# Driver_using_SON3x3_mosfet.net
KiCad netlist of a schematic drawn in Altium Designer
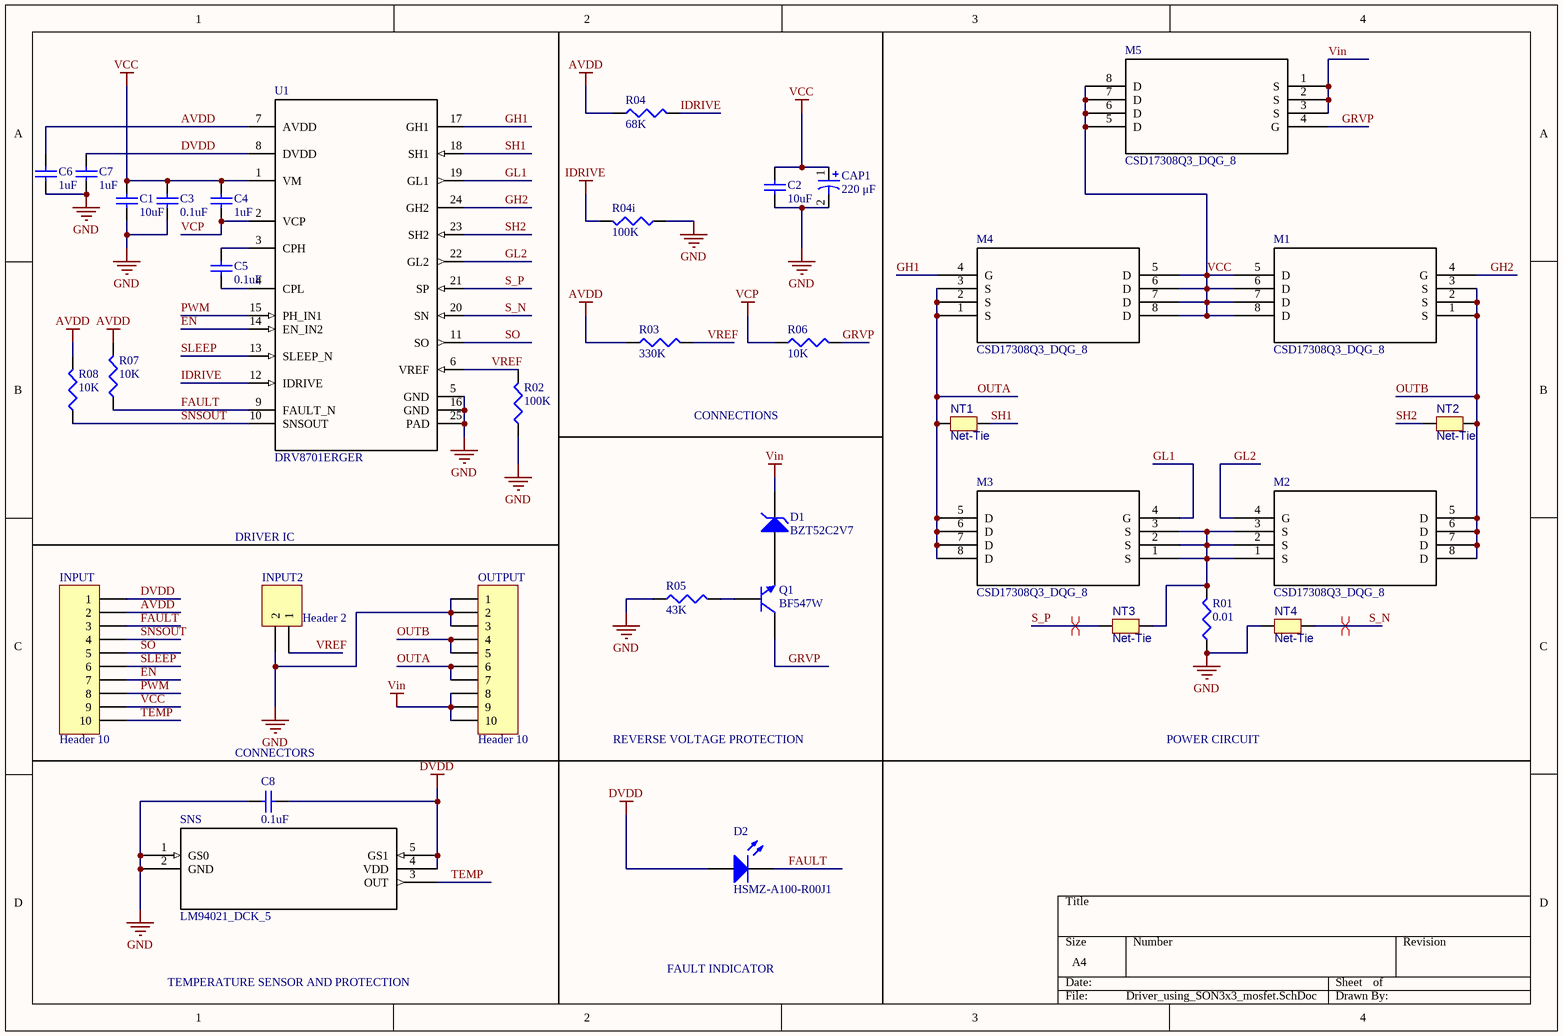
[diagram p0: Driver_using_SON3x3_mosfet.SchDoc]

(export (version "E")
  (design (tool "Eeschema 10.0.6"))
  (components
    (comp (ref "C1")
      (value "10uF")
      (footprint "C1210")
      (description "Capacitor (Semiconductor SIM Model)")
      (fields (field (name "PUBLISHER") "Altium Limited"))
      (libsource (lib "Miscellaneous Devices") (part "Cap Semi"))
    )
    (comp (ref "C2")
      (value "10uF")
      (footprint "C1210")
      (description "Capacitor (Semiconductor SIM Model)")
      (fields (field (name "PUBLISHER") "Altium Limited"))
      (libsource (lib "Miscellaneous Devices") (part "Cap Semi"))
    )
    (comp (ref "C3")
      (value "0.1uF")
      (footprint "1608[0603]")
      (description "Capacitor (Semiconductor SIM Model)")
      (fields (field (name "PUBLISHER") "Altium Limited"))
      (libsource (lib "Miscellaneous Devices") (part "Cap Semi"))
    )
    (comp (ref "C4")
      (value "1uF")
      (footprint "1608[0603]")
      (description "Capacitor (Semiconductor SIM Model)")
      (fields (field (name "PUBLISHER") "Altium Limited"))
      (libsource (lib "Miscellaneous Devices") (part "Cap Semi"))
    )
    (comp (ref "C5")
      (value "0.1uF")
      (footprint "1608[0603]")
      (description "Capacitor (Semiconductor SIM Model)")
      (fields (field (name "PUBLISHER") "Altium Limited"))
      (libsource (lib "Miscellaneous Devices") (part "Cap Semi"))
    )
    (comp (ref "C6")
      (value "1uF")
      (footprint "1608[0603]")
      (description "Capacitor (Semiconductor SIM Model)")
      (fields (field (name "PUBLISHER") "Altium Limited"))
      (libsource (lib "Miscellaneous Devices") (part "Cap Semi"))
    )
    (comp (ref "C7")
      (value "1uF")
      (footprint "1608[0603]")
      (description "Capacitor (Semiconductor SIM Model)")
      (fields (field (name "PUBLISHER") "Altium Limited"))
      (libsource (lib "Miscellaneous Devices") (part "Cap Semi"))
    )
    (comp (ref "C8")
      (value "0.1uF")
      (footprint "1608[0603]")
      (description "Capacitor (Semiconductor SIM Model)")
      (fields (field (name "PUBLISHER") "Altium Limited"))
      (libsource (lib "Miscellaneous Devices") (part "Cap Semi"))
    )
    (comp (ref "CAP1")
      (value "220 μF")
      (footprint "WCAP-ASLL 10x10.5x4.5")
      (description "WCAP-ASLL Aluminum Electrolytic Capacitors , 220 μF; + / - 20%; 35 V , 10 x 10,5")
      (fields
        (field (name "MANUFACTURER") "Wurth Elektronik")
        (field (name "PARTNO") "865060557008")
        (field (name "E-MAIL") "libraries@we-online.com")
        (field (name "CREATED BY") "Karrer Zheng")
      )
      (libsource (lib "WCAP-ASLL_rev15a") (part "WCAP-ASLL 10x10.5x4.5 865060557008"))
    )
    (comp (ref "D1")
      (value "BZT52C2V7")
      (footprint "SOD-123")
      (description "Surface Mount Zener Diode")
      (fields (field (name "PUBLISHER") "Altium Limited"))
      (libsource (lib "Vishay Lite-On Discrete Diode") (part "BZT52C2V7"))
    )
    (comp (ref "D2")
      (value "HSMZ-A100-R00J1")
      (footprint "3.5X2.8X1.9")
      (description "Surface Mount LED Indicator, Red")
      (fields (field (name "PUBLISHER") "Altium Limited"))
      (libsource (lib "Avago Optoelectronic LED") (part "HSMZ-A100-R00J1"))
    )
    (comp (ref "INPUT")
      (value "Header 10")
      (footprint "HDR1X10")
      (description "Header, 10-Pin")
      (fields (field (name "PUBLISHER") "Altium Limited"))
      (libsource (lib "Miscellaneous Connectors") (part "Header 10"))
    )
    (comp (ref "INPUT2")
      (value "Header 2")
      (footprint "HDR1X2")
      (description "Header, 2-Pin")
      (fields (field (name "PUBLISHER") "Altium Limited"))
      (libsource (lib "Miscellaneous Connectors") (part "Header 2"))
    )
    (comp (ref "M1")
      (value "CSD17308Q3_DQG_8")
      (footprint "DQG8")
      (description "Imported")
      (fields
        (field (name "MANUFACTURER") "Texas Instruments")
        (field (name "GENERIC_PART_NUMBER") "CSD17308Q3")
      )
      (libsource (lib "2016-01-31_14-51-58") (part "CSD17308Q3_DQG_8"))
    )
    (comp (ref "M2")
      (value "CSD17308Q3_DQG_8")
      (footprint "DQG8")
      (description "Imported")
      (fields
        (field (name "MANUFACTURER") "Texas Instruments")
        (field (name "GENERIC_PART_NUMBER") "CSD17308Q3")
      )
      (libsource (lib "2016-01-31_14-51-58") (part "CSD17308Q3_DQG_8"))
    )
    (comp (ref "M3")
      (value "CSD17308Q3_DQG_8")
      (footprint "DQG8")
      (description "Imported")
      (fields
        (field (name "MANUFACTURER") "Texas Instruments")
        (field (name "GENERIC_PART_NUMBER") "CSD17308Q3")
      )
      (libsource (lib "2016-01-31_14-51-58") (part "CSD17308Q3_DQG_8"))
    )
    (comp (ref "M4")
      (value "CSD17308Q3_DQG_8")
      (footprint "DQG8")
      (description "Imported")
      (fields
        (field (name "MANUFACTURER") "Texas Instruments")
        (field (name "GENERIC_PART_NUMBER") "CSD17308Q3")
      )
      (libsource (lib "2016-01-31_14-51-58") (part "CSD17308Q3_DQG_8"))
    )
    (comp (ref "M5")
      (value "CSD17308Q3_DQG_8")
      (footprint "DQG8")
      (description "Imported")
      (fields
        (field (name "MANUFACTURER") "Texas Instruments")
        (field (name "GENERIC_PART_NUMBER") "CSD17308Q3")
      )
      (libsource (lib "2016-01-31_14-51-58") (part "CSD17308Q3_DQG_8"))
    )
    (comp (ref "NT1")
      (value "Net-Tie")
      (footprint "NetTieLib:2way_LP")
      (description "Single point connection between nets.")
      (fields (field (name "SYMBOLCREATOR") "codlsc") (field (name "PUBLISHER") "Texas Instruments"))
      (libsource (lib "MiscParts") (part "Net-Tie"))
    )
    (comp (ref "NT2")
      (value "Net-Tie")
      (footprint "2way_LP")
      (description "Single point connection between nets.")
      (fields (field (name "SYMBOLCREATOR") "codlsc") (field (name "PUBLISHER") "Texas Instruments"))
      (libsource (lib "MiscParts") (part "Net-Tie"))
    )
    (comp (ref "NT3")
      (value "Net-Tie")
      (footprint "2way_LP")
      (description "Single point connection between nets.")
      (fields (field (name "SYMBOLCREATOR") "codlsc") (field (name "PUBLISHER") "Texas Instruments"))
      (libsource (lib "MiscParts") (part "Net-Tie"))
    )
    (comp (ref "NT4")
      (value "Net-Tie")
      (footprint "2way_LP")
      (description "Single point connection between nets.")
      (fields (field (name "SYMBOLCREATOR") "codlsc") (field (name "PUBLISHER") "Texas Instruments"))
      (libsource (lib "MiscParts") (part "Net-Tie"))
    )
    (comp (ref "OUTPUT")
      (value "Header 10")
      (footprint "HDR1X10")
      (description "Header, 10-Pin")
      (fields (field (name "PUBLISHER") "Altium Limited"))
      (libsource (lib "") (part "Header 10_1"))
    )
    (comp (ref "Q1")
      (value "BF547W")
      (footprint "SOT323_N")
      (description "NPN 1 GHz Wideband Transistor")
      (fields (field (name "PUBLISHER") "Altium Limited"))
      (libsource (lib "Philips Discrete BJT - RF Transistor") (part "BF547W"))
    )
    (comp (ref "R01")
      (value "0.01")
      (footprint "14-1210")
      (description "Resistor")
      (fields (field (name "PUBLISHER") "Altium Limited"))
      (libsource (lib "Miscellaneous Devices") (part "Res3"))
    )
    (comp (ref "R02")
      (value "100K")
      (footprint "J1-0603")
      (description "Resistor")
      (fields (field (name "PUBLISHER") "Altium Limited"))
      (libsource (lib "Miscellaneous Devices") (part "Res3"))
    )
    (comp (ref "R03")
      (value "330K")
      (footprint "J1-0603")
      (description "Resistor")
      (fields (field (name "PUBLISHER") "Altium Limited"))
      (libsource (lib "Miscellaneous Devices") (part "Res3"))
    )
    (comp (ref "R04")
      (value "68K")
      (footprint "J1-0603")
      (description "Resistor")
      (fields (field (name "PUBLISHER") "Altium Limited"))
      (libsource (lib "Miscellaneous Devices") (part "Res3"))
    )
    (comp (ref "R04i")
      (value "100K")
      (footprint "J1-0603")
      (description "Resistor")
      (fields (field (name "PUBLISHER") "Altium Limited"))
      (libsource (lib "Miscellaneous Devices") (part "Res3"))
    )
    (comp (ref "R05")
      (value "43K")
      (footprint "J1-0603")
      (description "Resistor")
      (fields (field (name "PUBLISHER") "Altium Limited"))
      (libsource (lib "Miscellaneous Devices") (part "Res3"))
    )
    (comp (ref "R06")
      (value "10K")
      (footprint "J1-0603")
      (description "Resistor")
      (fields (field (name "PUBLISHER") "Altium Limited"))
      (libsource (lib "Miscellaneous Devices") (part "Res3"))
    )
    (comp (ref "R07")
      (value "10K")
      (footprint "J1-0603")
      (description "Resistor")
      (fields (field (name "PUBLISHER") "Altium Limited"))
      (libsource (lib "Miscellaneous Devices") (part "Res3"))
    )
    (comp (ref "R08")
      (value "10K")
      (footprint "J1-0603")
      (description "Resistor")
      (fields (field (name "PUBLISHER") "Altium Limited"))
      (libsource (lib "Miscellaneous Devices") (part "Res3"))
    )
    (comp (ref "SNS")
      (value "LM94021_DCK_5")
      (footprint "MAA05A")
      (description "Imported")
      (fields
        (field (name "MANUFACTURER") "Texas Instruments")
        (field (name "MANUFACTURER_PART_NUMBER") "lm94021_dck_5")
      )
      (libsource (lib "2016-02-23_02-52-09") (part "LM94021_DCK_5"))
    )
    (comp (ref "U1")
      (value "DRV8701ERGER")
      (footprint "RGE0024F")
      (description "Imported")
      (fields
        (field (name "ALTERNATE PARTNUMBER") "DRV8701ERGET")
        (field (name "MANUFACTURER") "Texas Instruments")
      )
      (libsource (lib "2016-01-03_22-07-35") (part "DRV8701ERGER"))
    )
  )
  (nets
    (net (code "1") (name "/EN") (class "Default")
      (node (ref "INPUT") (pin "7") (pinfunction "7_7") (pintype "passive"))
      (node (ref "U1") (pin "14") (pinfunction "EN_IN2_14") (pintype "input"))
    )
    (net (code "2") (name "/FAULT") (class "Default")
      (node (ref "D2") (pin "2") (pinfunction "K_2") (pintype "passive"))
      (node (ref "INPUT") (pin "3") (pinfunction "3_3") (pintype "passive"))
      (node (ref "R07") (pin "1") (pinfunction "1_1") (pintype "passive"))
      (node (ref "U1") (pin "9") (pinfunction "FAULT_N_9") (pintype "open_collector"))
    )
    (net (code "3") (name "/GH1") (class "Default")
      (node (ref "M4") (pin "4") (pinfunction "G_4") (pintype "passive"))
      (node (ref "U1") (pin "17") (pinfunction "GH1_17") (pintype "power_in"))
    )
    (net (code "4") (name "/GH2") (class "Default")
      (node (ref "M1") (pin "4") (pinfunction "G_4") (pintype "passive"))
      (node (ref "U1") (pin "24") (pinfunction "GH2_24") (pintype "power_in"))
    )
    (net (code "5") (name "/GL1") (class "Default")
      (node (ref "M3") (pin "4") (pinfunction "G_4") (pintype "passive"))
      (node (ref "U1") (pin "19") (pinfunction "GL1_19") (pintype "output"))
    )
    (net (code "6") (name "/GL2") (class "Default")
      (node (ref "M2") (pin "4") (pinfunction "G_4") (pintype "passive"))
      (node (ref "U1") (pin "22") (pinfunction "GL2_22") (pintype "output"))
    )
    (net (code "7") (name "/GRVP") (class "Default")
      (node (ref "M5") (pin "4") (pinfunction "G_4") (pintype "passive"))
      (node (ref "Q1") (pin "3") (pinfunction "C_3") (pintype "passive"))
      (node (ref "R06") (pin "2") (pinfunction "2_2") (pintype "passive"))
    )
    (net (code "8") (name "/OUTA") (class "Default")
      (node (ref "M3") (pin "5") (pinfunction "D_5") (pintype "passive"))
      (node (ref "M3") (pin "6") (pinfunction "D_6") (pintype "passive"))
      (node (ref "M3") (pin "7") (pinfunction "D_7") (pintype "passive"))
      (node (ref "M3") (pin "8") (pinfunction "D_8") (pintype "passive"))
      (node (ref "M4") (pin "1") (pinfunction "S_1") (pintype "passive"))
      (node (ref "M4") (pin "2") (pinfunction "S_2") (pintype "passive"))
      (node (ref "M4") (pin "3") (pinfunction "S_3") (pintype "passive"))
      (node (ref "NT1") (pin "1") (pinfunction "1_1") (pintype "passive"))
      (node (ref "OUTPUT") (pin "6") (pinfunction "6_6") (pintype "passive"))
      (node (ref "OUTPUT") (pin "7") (pinfunction "7_7") (pintype "passive"))
    )
    (net (code "9") (name "/OUTB") (class "Default")
      (node (ref "M1") (pin "1") (pinfunction "S_1") (pintype "passive"))
      (node (ref "M1") (pin "2") (pinfunction "S_2") (pintype "passive"))
      (node (ref "M1") (pin "3") (pinfunction "S_3") (pintype "passive"))
      (node (ref "M2") (pin "5") (pinfunction "D_5") (pintype "passive"))
      (node (ref "M2") (pin "6") (pinfunction "D_6") (pintype "passive"))
      (node (ref "M2") (pin "7") (pinfunction "D_7") (pintype "passive"))
      (node (ref "M2") (pin "8") (pinfunction "D_8") (pintype "passive"))
      (node (ref "NT2") (pin "2") (pinfunction "2_2") (pintype "passive"))
      (node (ref "OUTPUT") (pin "4") (pinfunction "4_4") (pintype "passive"))
      (node (ref "OUTPUT") (pin "5") (pinfunction "5_5") (pintype "passive"))
    )
    (net (code "10") (name "/PWM") (class "Default")
      (node (ref "INPUT") (pin "8") (pinfunction "8_8") (pintype "passive"))
      (node (ref "U1") (pin "15") (pinfunction "PH_IN1_15") (pintype "input"))
    )
    (net (code "11") (name "/SH1") (class "Default")
      (node (ref "NT1") (pin "2") (pinfunction "2_2") (pintype "passive"))
      (node (ref "U1") (pin "18") (pinfunction "SH1_18") (pintype "input"))
    )
    (net (code "12") (name "/SH2") (class "Default")
      (node (ref "NT2") (pin "1") (pinfunction "1_1") (pintype "passive"))
      (node (ref "U1") (pin "23") (pinfunction "SH2_23") (pintype "input"))
    )
    (net (code "13") (name "/SLEEP") (class "Default")
      (node (ref "INPUT") (pin "6") (pinfunction "6_6") (pintype "passive"))
      (node (ref "U1") (pin "13") (pinfunction "SLEEP_N_13") (pintype "input"))
    )
    (net (code "14") (name "/SNSOUT") (class "Default")
      (node (ref "INPUT") (pin "4") (pinfunction "4_4") (pintype "passive"))
      (node (ref "R08") (pin "1") (pinfunction "1_1") (pintype "passive"))
      (node (ref "U1") (pin "10") (pinfunction "SNSOUT_10") (pintype "open_collector"))
    )
    (net (code "15") (name "/SO") (class "Default")
      (node (ref "INPUT") (pin "5") (pinfunction "5_5") (pintype "passive"))
      (node (ref "U1") (pin "11") (pinfunction "SO_11") (pintype "output"))
    )
    (net (code "16") (name "/S_N") (class "Default")
      (node (ref "NT4") (pin "2") (pinfunction "2_2") (pintype "passive"))
      (node (ref "U1") (pin "20") (pinfunction "SN_20") (pintype "input"))
    )
    (net (code "17") (name "/S_P") (class "Default")
      (node (ref "NT3") (pin "1") (pinfunction "1_1") (pintype "passive"))
      (node (ref "U1") (pin "21") (pinfunction "SP_21") (pintype "input"))
    )
    (net (code "18") (name "/TEMP") (class "Default")
      (node (ref "INPUT") (pin "10") (pinfunction "10_10") (pintype "passive"))
      (node (ref "SNS") (pin "3") (pinfunction "OUT_3") (pintype "output"))
    )
    (net (code "19") (name "/VREF") (class "Default")
      (node (ref "INPUT2") (pin "1") (pinfunction "1_1") (pintype "passive"))
      (node (ref "R02") (pin "2") (pinfunction "2_2") (pintype "passive"))
      (node (ref "R03") (pin "2") (pinfunction "2_2") (pintype "passive"))
      (node (ref "U1") (pin "6") (pinfunction "VREF_6") (pintype "input"))
    )
    (net (code "20") (name "AVDD") (class "Default")
      (node (ref "C6") (pin "1") (pinfunction "1_1") (pintype "passive"))
      (node (ref "INPUT") (pin "2") (pinfunction "2_2") (pintype "passive"))
      (node (ref "R03") (pin "1") (pinfunction "1_1") (pintype "passive"))
      (node (ref "R04") (pin "1") (pinfunction "1_1") (pintype "passive"))
      (node (ref "R07") (pin "2") (pinfunction "2_2") (pintype "passive"))
      (node (ref "R08") (pin "2") (pinfunction "2_2") (pintype "passive"))
      (node (ref "U1") (pin "7") (pinfunction "AVDD_7") (pintype "power_in"))
    )
    (net (code "21") (name "DVDD") (class "Default")
      (node (ref "C7") (pin "1") (pinfunction "1_1") (pintype "passive"))
      (node (ref "C8") (pin "1") (pinfunction "1_1") (pintype "passive"))
      (node (ref "D2") (pin "1") (pinfunction "A_1") (pintype "passive"))
      (node (ref "INPUT") (pin "1") (pinfunction "1_1") (pintype "passive"))
      (node (ref "SNS") (pin "4") (pinfunction "VDD_4") (pintype "power_in"))
      (node (ref "SNS") (pin "5") (pinfunction "GS1_5") (pintype "input"))
      (node (ref "U1") (pin "8") (pinfunction "DVDD_8") (pintype "power_in"))
    )
    (net (code "22") (name "GND") (class "Default")
      (node (ref "C1") (pin "1") (pinfunction "1_1") (pintype "passive"))
      (node (ref "C2") (pin "1") (pinfunction "1_1") (pintype "passive"))
      (node (ref "C3") (pin "1") (pinfunction "1_1") (pintype "passive"))
      (node (ref "C6") (pin "2") (pinfunction "2_2") (pintype "passive"))
      (node (ref "C7") (pin "2") (pinfunction "2_2") (pintype "passive"))
      (node (ref "C8") (pin "2") (pinfunction "2_2") (pintype "passive"))
      (node (ref "CAP1") (pin "2") (pinfunction "2_2") (pintype "passive"))
      (node (ref "INPUT2") (pin "2") (pinfunction "2_2") (pintype "passive"))
      (node (ref "NT4") (pin "1") (pinfunction "1_1") (pintype "passive"))
      (node (ref "OUTPUT") (pin "1") (pinfunction "1_1") (pintype "passive"))
      (node (ref "OUTPUT") (pin "2") (pinfunction "2_2") (pintype "passive"))
      (node (ref "OUTPUT") (pin "3") (pinfunction "3_3") (pintype "passive"))
      (node (ref "R01") (pin "1") (pinfunction "1_1") (pintype "passive"))
      (node (ref "R02") (pin "1") (pinfunction "1_1") (pintype "passive"))
      (node (ref "R04i") (pin "1") (pinfunction "1_1") (pintype "passive"))
      (node (ref "R05") (pin "1") (pinfunction "1_1") (pintype "passive"))
      (node (ref "SNS") (pin "1") (pinfunction "GS0_1") (pintype "input"))
      (node (ref "SNS") (pin "2") (pinfunction "GND_2") (pintype "power_in"))
      (node (ref "U1") (pin "16") (pinfunction "GND_16") (pintype "power_in"))
      (node (ref "U1") (pin "25") (pinfunction "PAD_25") (pintype "power_in"))
      (node (ref "U1") (pin "5") (pinfunction "GND_5") (pintype "power_in"))
    )
    (net (code "23") (name "IDRIVE") (class "Default")
      (node (ref "R04") (pin "2") (pinfunction "2_2") (pintype "passive"))
      (node (ref "R04i") (pin "2") (pinfunction "2_2") (pintype "passive"))
      (node (ref "U1") (pin "12") (pinfunction "IDRIVE_12") (pintype "input"))
    )
    (net (code "24") (name "Net-(D1-A)") (class "Default")
      (node (ref "D1") (pin "1") (pinfunction "A_1") (pintype "passive"))
      (node (ref "Q1") (pin "2") (pinfunction "E_2") (pintype "passive"))
    )
    (net (code "25") (name "Net-(M2-S-Pad1)") (class "Default")
      (node (ref "M2") (pin "1") (pinfunction "S_1") (pintype "passive"))
      (node (ref "M2") (pin "2") (pinfunction "S_2") (pintype "passive"))
      (node (ref "M2") (pin "3") (pinfunction "S_3") (pintype "passive"))
      (node (ref "M3") (pin "1") (pinfunction "S_1") (pintype "passive"))
      (node (ref "M3") (pin "2") (pinfunction "S_2") (pintype "passive"))
      (node (ref "M3") (pin "3") (pinfunction "S_3") (pintype "passive"))
      (node (ref "NT3") (pin "2") (pinfunction "2_2") (pintype "passive"))
      (node (ref "R01") (pin "2") (pinfunction "2_2") (pintype "passive"))
    )
    (net (code "26") (name "Net-(Q1-B)") (class "Default")
      (node (ref "Q1") (pin "1") (pinfunction "B_1") (pintype "passive"))
      (node (ref "R05") (pin "2") (pinfunction "2_2") (pintype "passive"))
    )
    (net (code "27") (name "Net-(U1-CPH)") (class "Default")
      (node (ref "C5") (pin "2") (pinfunction "2_2") (pintype "passive"))
      (node (ref "U1") (pin "3") (pinfunction "CPH_3") (pintype "passive"))
    )
    (net (code "28") (name "Net-(U1-CPL)") (class "Default")
      (node (ref "C5") (pin "1") (pinfunction "1_1") (pintype "passive"))
      (node (ref "U1") (pin "4") (pinfunction "CPL_4") (pintype "passive"))
    )
    (net (code "29") (name "VCC") (class "Default")
      (node (ref "C1") (pin "2") (pinfunction "2_2") (pintype "passive"))
      (node (ref "C2") (pin "2") (pinfunction "2_2") (pintype "passive"))
      (node (ref "C3") (pin "2") (pinfunction "2_2") (pintype "passive"))
      (node (ref "C4") (pin "1") (pinfunction "1_1") (pintype "passive"))
      (node (ref "CAP1") (pin "1") (pinfunction "1_1") (pintype "passive"))
      (node (ref "INPUT") (pin "9") (pinfunction "9_9") (pintype "passive"))
      (node (ref "M1") (pin "5") (pinfunction "D_5") (pintype "passive"))
      (node (ref "M1") (pin "6") (pinfunction "D_6") (pintype "passive"))
      (node (ref "M1") (pin "7") (pinfunction "D_7") (pintype "passive"))
      (node (ref "M1") (pin "8") (pinfunction "D_8") (pintype "passive"))
      (node (ref "M4") (pin "5") (pinfunction "D_5") (pintype "passive"))
      (node (ref "M4") (pin "6") (pinfunction "D_6") (pintype "passive"))
      (node (ref "M4") (pin "7") (pinfunction "D_7") (pintype "passive"))
      (node (ref "M4") (pin "8") (pinfunction "D_8") (pintype "passive"))
      (node (ref "M5") (pin "5") (pinfunction "D_5") (pintype "passive"))
      (node (ref "M5") (pin "6") (pinfunction "D_6") (pintype "passive"))
      (node (ref "M5") (pin "7") (pinfunction "D_7") (pintype "passive"))
      (node (ref "M5") (pin "8") (pinfunction "D_8") (pintype "passive"))
      (node (ref "U1") (pin "1") (pinfunction "VM_1") (pintype "power_in"))
    )
    (net (code "30") (name "VCP") (class "Default")
      (node (ref "C4") (pin "2") (pinfunction "2_2") (pintype "passive"))
      (node (ref "R06") (pin "1") (pinfunction "1_1") (pintype "passive"))
      (node (ref "U1") (pin "2") (pinfunction "VCP_2") (pintype "power_in"))
    )
    (net (code "31") (name "Vin") (class "Default")
      (node (ref "D1") (pin "2") (pinfunction "K_2") (pintype "passive"))
      (node (ref "M5") (pin "1") (pinfunction "S_1") (pintype "passive"))
      (node (ref "M5") (pin "2") (pinfunction "S_2") (pintype "passive"))
      (node (ref "M5") (pin "3") (pinfunction "S_3") (pintype "passive"))
      (node (ref "OUTPUT") (pin "10") (pinfunction "10_10") (pintype "passive"))
      (node (ref "OUTPUT") (pin "8") (pinfunction "8_8") (pintype "passive"))
      (node (ref "OUTPUT") (pin "9") (pinfunction "9_9") (pintype "passive"))
    )
  )
)
